# controllerHatMini.net
KiCad netlist of a schematic drawn in EAGLE
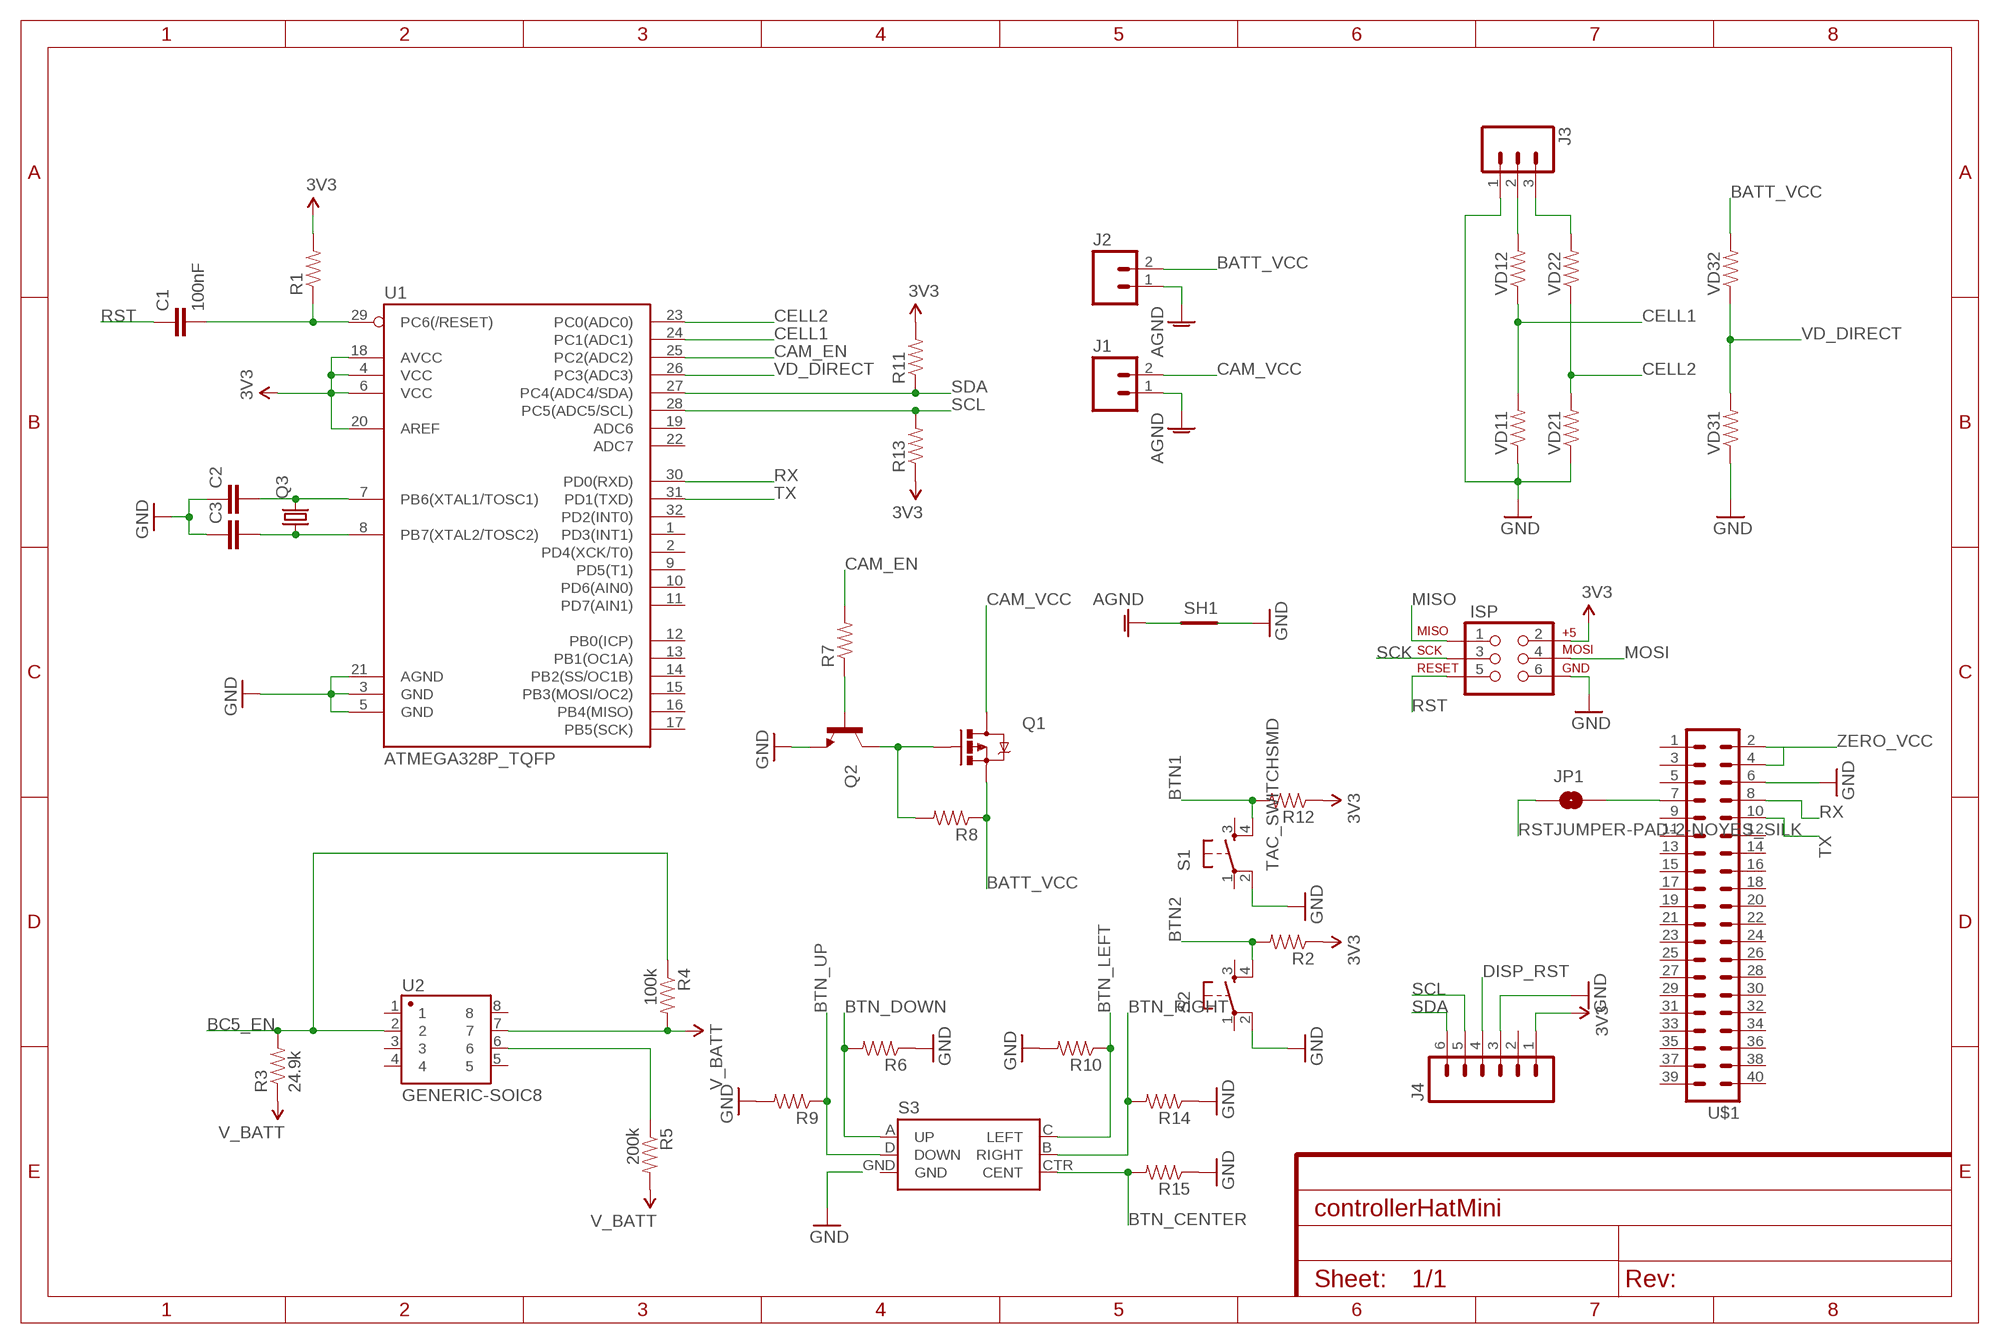
[diagram p0: schematic, sheet 1]

(export (version "E")
  (design (tool "Eeschema 10.0.6"))
  (components
    (comp (ref "C1")
      (value "100nF")
      (footprint "eagle-import:1206")
      (libsource (lib "eagle-import") (part "CAP1206"))
    )
    (comp (ref "C2")
      (value "CAP1206")
      (footprint "eagle-import:1206")
      (libsource (lib "eagle-import") (part "CAP1206"))
    )
    (comp (ref "C3")
      (value "CAP1206")
      (footprint "eagle-import:1206")
      (libsource (lib "eagle-import") (part "CAP1206"))
    )
    (comp (ref "ISP")
      (value "AVR_SPI_PRG_6PTH")
      (footprint "eagle-import:2X3")
      (libsource (lib "eagle-import") (part "AVR_SPI_PRG_6PTH"))
    )
    (comp (ref "J1")
      (value "M023.5MM_LOCK")
      (footprint "eagle-import:SCREWTERMINAL-3.5MM-2_LOCK")
      (libsource (lib "eagle-import") (part "M023.5MM_LOCK"))
    )
    (comp (ref "J2")
      (value "M023.5MM_LOCK")
      (footprint "eagle-import:SCREWTERMINAL-3.5MM-2_LOCK")
      (libsource (lib "eagle-import") (part "M023.5MM_LOCK"))
    )
    (comp (ref "J3")
      (value "M03LOCK")
      (footprint "eagle-import:1X03_LOCK")
      (libsource (lib "eagle-import") (part "M03LOCK"))
    )
    (comp (ref "J4")
      (value "M06LOCK")
      (footprint "eagle-import:1X06_LOCK")
      (libsource (lib "eagle-import") (part "M06LOCK"))
    )
    (comp (ref "JP1")
      (value "JUMPER-PAD-2-NOYES_SILK")
      (footprint "eagle-import:PAD-JUMPER-2-NO_YES_SILK")
      (libsource (lib "eagle-import") (part "JUMPER-PAD-2-NOYES_SILK"))
    )
    (comp (ref "Q1")
      (value "MOSFET-PCHANNELNDP6020P_20V_24A_LOW_VGS_TH")
      (footprint "eagle-import:TO220V")
      (libsource (lib "eagle-import") (part "MOSFET-PCHANNELNDP6020P_20V_24A_LOW_VGS_TH"))
    )
    (comp (ref "Q2")
      (value "TRANSISTOR_NPN2N3904")
      (footprint "eagle-import:TO-92")
      (libsource (lib "eagle-import") (part "TRANSISTOR_NPN2N3904"))
    )
    (comp (ref "Q3")
      (value "CRYSTALMM20SS")
      (footprint "eagle-import:MM20SS")
      (libsource (lib "eagle-import") (part "CRYSTALMM20SS"))
    )
    (comp (ref "R1")
      (value "RESISTOR1206")
      (footprint "eagle-import:1206")
      (libsource (lib "eagle-import") (part "RESISTOR1206"))
    )
    (comp (ref "R2")
      (value "RESISTOR1206")
      (footprint "eagle-import:1206")
      (libsource (lib "eagle-import") (part "RESISTOR1206"))
    )
    (comp (ref "R3")
      (value "24.9k")
      (footprint "eagle-import:1206")
      (libsource (lib "eagle-import") (part "RESISTOR1206"))
    )
    (comp (ref "R4")
      (value "100k")
      (footprint "eagle-import:1206")
      (libsource (lib "eagle-import") (part "RESISTOR1206"))
    )
    (comp (ref "R5")
      (value "200k")
      (footprint "eagle-import:1206")
      (libsource (lib "eagle-import") (part "RESISTOR1206"))
    )
    (comp (ref "R6")
      (value "RESISTOR1206")
      (footprint "eagle-import:1206")
      (libsource (lib "eagle-import") (part "RESISTOR1206"))
    )
    (comp (ref "R7")
      (value "RESISTOR1206")
      (footprint "eagle-import:1206")
      (libsource (lib "eagle-import") (part "RESISTOR1206"))
    )
    (comp (ref "R8")
      (value "RESISTOR1206")
      (footprint "eagle-import:1206")
      (libsource (lib "eagle-import") (part "RESISTOR1206"))
    )
    (comp (ref "R9")
      (value "RESISTOR1206")
      (footprint "eagle-import:1206")
      (libsource (lib "eagle-import") (part "RESISTOR1206"))
    )
    (comp (ref "R10")
      (value "RESISTOR1206")
      (footprint "eagle-import:1206")
      (libsource (lib "eagle-import") (part "RESISTOR1206"))
    )
    (comp (ref "R11")
      (value "RESISTOR1206")
      (footprint "eagle-import:1206")
      (libsource (lib "eagle-import") (part "RESISTOR1206"))
    )
    (comp (ref "R12")
      (value "RESISTOR1206")
      (footprint "eagle-import:1206")
      (libsource (lib "eagle-import") (part "RESISTOR1206"))
    )
    (comp (ref "R13")
      (value "RESISTOR1206")
      (footprint "eagle-import:1206")
      (libsource (lib "eagle-import") (part "RESISTOR1206"))
    )
    (comp (ref "R14")
      (value "RESISTOR1206")
      (footprint "eagle-import:1206")
      (libsource (lib "eagle-import") (part "RESISTOR1206"))
    )
    (comp (ref "R15")
      (value "RESISTOR1206")
      (footprint "eagle-import:1206")
      (libsource (lib "eagle-import") (part "RESISTOR1206"))
    )
    (comp (ref "S1")
      (value "TAC_SWITCHSMD")
      (footprint "eagle-import:TACTILE-PTH")
      (libsource (lib "eagle-import") (part "TAC_SWITCHPTH"))
    )
    (comp (ref "S2")
      (value "TAC_SWITCHPTH")
      (footprint "eagle-import:TACTILE-PTH")
      (libsource (lib "eagle-import") (part "TAC_SWITCHPTH"))
    )
    (comp (ref "S3")
      (value "JOYSTICK_MINI")
      (footprint "eagle-import:JOYSTICK_MINI")
      (libsource (lib "eagle-import") (part "JOYSTICK_MINI"))
    )
    (comp (ref "SH1")
      (value "SHORT-HT5")
      (footprint "eagle-import:SHORT_TOP-50")
      (libsource (lib "eagle-import") (part "SHORT-HT5"))
    )
    (comp (ref "U$1")
      (value "PIZERO_THROUGH_HOLE")
      (footprint "eagle-import:PIZERO_THOUGH_HOLE")
      (libsource (lib "eagle-import") (part "PIZERO_THROUGH_HOLE"))
    )
    (comp (ref "U1")
      (value "ATMEGA328P_TQFP")
      (footprint "eagle-import:TQFP32-08")
      (libsource (lib "eagle-import") (part "ATMEGA328P_TQFP"))
    )
    (comp (ref "U2")
      (value "GENERIC-SOIC8")
      (footprint "eagle-import:SO08-UNIVERSAL")
      (libsource (lib "eagle-import") (part "GENERIC-SOIC8"))
    )
    (comp (ref "VD11")
      (value "RESISTOR1206")
      (footprint "eagle-import:1206")
      (libsource (lib "eagle-import") (part "RESISTOR1206"))
    )
    (comp (ref "VD12")
      (value "RESISTOR1206")
      (footprint "eagle-import:1206")
      (libsource (lib "eagle-import") (part "RESISTOR1206"))
    )
    (comp (ref "VD21")
      (value "RESISTOR1206")
      (footprint "eagle-import:1206")
      (libsource (lib "eagle-import") (part "RESISTOR1206"))
    )
    (comp (ref "VD22")
      (value "RESISTOR1206")
      (footprint "eagle-import:1206")
      (libsource (lib "eagle-import") (part "RESISTOR1206"))
    )
    (comp (ref "VD31")
      (value "RESISTOR1206")
      (footprint "eagle-import:1206")
      (libsource (lib "eagle-import") (part "RESISTOR1206"))
    )
    (comp (ref "VD32")
      (value "RESISTOR1206")
      (footprint "eagle-import:1206")
      (libsource (lib "eagle-import") (part "RESISTOR1206"))
    )
  )
  (nets
    (net (code "1") (name "/BATT_VCC") (class "Default")
      (node (ref "J2") (pin "2") (pinfunction "2_2") (pintype "passive"))
      (node (ref "Q1") (pin "3") (pinfunction "S_3") (pintype "passive"))
      (node (ref "R8") (pin "1") (pinfunction "1_1") (pintype "passive"))
      (node (ref "VD32") (pin "2") (pinfunction "2_2") (pintype "passive"))
    )
    (net (code "2") (name "/BC5_EN") (class "Default")
      (node (ref "R3") (pin "2") (pinfunction "2_2") (pintype "passive"))
      (node (ref "R4") (pin "1") (pinfunction "1_1") (pintype "passive"))
      (node (ref "U2") (pin "2") (pinfunction "2_2") (pintype "bidirectional"))
    )
    (net (code "3") (name "/BTN1") (class "Default")
      (node (ref "R12") (pin "2") (pinfunction "2_2") (pintype "passive"))
      (node (ref "S1") (pin "4") (pinfunction "4_4") (pintype "passive"))
    )
    (net (code "4") (name "/BTN2") (class "Default")
      (node (ref "R2") (pin "2") (pinfunction "2_2") (pintype "passive"))
      (node (ref "S2") (pin "4") (pinfunction "4_4") (pintype "passive"))
    )
    (net (code "5") (name "/BTN_CENTER") (class "Default")
      (node (ref "R15") (pin "2") (pinfunction "2_2") (pintype "passive"))
      (node (ref "S3") (pin "CTR") (pinfunction "CENT_CTR") (pintype "bidirectional"))
    )
    (net (code "6") (name "/BTN_DOWN") (class "Default")
      (node (ref "R6") (pin "2") (pinfunction "2_2") (pintype "passive"))
      (node (ref "S3") (pin "A") (pinfunction "UP_A") (pintype "bidirectional"))
    )
    (net (code "7") (name "/BTN_LEFT") (class "Default")
      (node (ref "R10") (pin "1") (pinfunction "1_1") (pintype "passive"))
      (node (ref "S3") (pin "C") (pinfunction "LEFT_C") (pintype "bidirectional"))
    )
    (net (code "8") (name "/BTN_RIGHT") (class "Default")
      (node (ref "R14") (pin "2") (pinfunction "2_2") (pintype "passive"))
      (node (ref "S3") (pin "B") (pinfunction "RIGHT_B") (pintype "bidirectional"))
    )
    (net (code "9") (name "/BTN_UP") (class "Default")
      (node (ref "R9") (pin "1") (pinfunction "1_1") (pintype "passive"))
      (node (ref "S3") (pin "D") (pinfunction "DOWN_D") (pintype "bidirectional"))
    )
    (net (code "10") (name "/CAM_EN") (class "Default")
      (node (ref "R7") (pin "2") (pinfunction "2_2") (pintype "passive"))
      (node (ref "U1") (pin "25") (pinfunction "PC2(ADC2)_25") (pintype "bidirectional"))
    )
    (net (code "11") (name "/CAM_VCC") (class "Default")
      (node (ref "J1") (pin "2") (pinfunction "2_2") (pintype "passive"))
      (node (ref "Q1") (pin "2") (pinfunction "D_2") (pintype "passive"))
    )
    (net (code "12") (name "/CELL1") (class "Default")
      (node (ref "U1") (pin "24") (pinfunction "PC1(ADC1)_24") (pintype "bidirectional"))
      (node (ref "VD11") (pin "2") (pinfunction "2_2") (pintype "passive"))
      (node (ref "VD12") (pin "1") (pinfunction "1_1") (pintype "passive"))
    )
    (net (code "13") (name "/CELL2") (class "Default")
      (node (ref "U1") (pin "23") (pinfunction "PC0(ADC0)_23") (pintype "bidirectional"))
      (node (ref "VD21") (pin "2") (pinfunction "2_2") (pintype "passive"))
      (node (ref "VD22") (pin "1") (pinfunction "1_1") (pintype "passive"))
    )
    (net (code "14") (name "/DISP_RST") (class "Default")
      (node (ref "J4") (pin "4") (pinfunction "4_4") (pintype "passive"))
    )
    (net (code "15") (name "/MISO") (class "Default")
      (node (ref "ISP") (pin "1") (pinfunction "1_1") (pintype "passive"))
    )
    (net (code "16") (name "/MOSI") (class "Default")
      (node (ref "ISP") (pin "4") (pinfunction "4_4") (pintype "passive"))
    )
    (net (code "17") (name "/RST") (class "Default")
      (node (ref "C1") (pin "1") (pinfunction "1_1") (pintype "passive"))
      (node (ref "ISP") (pin "5") (pinfunction "5_5") (pintype "passive"))
      (node (ref "JP1") (pin "1") (pinfunction "1_1") (pintype "passive"))
    )
    (net (code "18") (name "/RX") (class "Default")
      (node (ref "U$1") (pin "8") (pinfunction "8_8") (pintype "passive"))
      (node (ref "U1") (pin "30") (pinfunction "PD0(RXD)_30") (pintype "bidirectional"))
    )
    (net (code "19") (name "/SCK") (class "Default")
      (node (ref "ISP") (pin "3") (pinfunction "3_3") (pintype "passive"))
    )
    (net (code "20") (name "/SCL") (class "Default")
      (node (ref "J4") (pin "5") (pinfunction "5_5") (pintype "passive"))
      (node (ref "R13") (pin "2") (pinfunction "2_2") (pintype "passive"))
      (node (ref "U1") (pin "28") (pinfunction "PC5(ADC5/SCL)_28") (pintype "bidirectional"))
    )
    (net (code "21") (name "/SDA") (class "Default")
      (node (ref "J4") (pin "6") (pinfunction "6_6") (pintype "passive"))
      (node (ref "R11") (pin "1") (pinfunction "1_1") (pintype "passive"))
      (node (ref "U1") (pin "27") (pinfunction "PC4(ADC4/SDA)_27") (pintype "bidirectional"))
    )
    (net (code "22") (name "/TX") (class "Default")
      (node (ref "U$1") (pin "10") (pinfunction "10_10") (pintype "passive"))
      (node (ref "U1") (pin "31") (pinfunction "PD1(TXD)_31") (pintype "bidirectional"))
    )
    (net (code "23") (name "/VD_DIRECT") (class "Default")
      (node (ref "U1") (pin "26") (pinfunction "PC3(ADC3)_26") (pintype "bidirectional"))
      (node (ref "VD31") (pin "2") (pinfunction "2_2") (pintype "passive"))
      (node (ref "VD32") (pin "1") (pinfunction "1_1") (pintype "passive"))
    )
    (net (code "24") (name "/ZERO_VCC") (class "Default")
      (node (ref "U$1") (pin "2") (pinfunction "2_2") (pintype "passive"))
    )
    (net (code "25") (name "3V3") (class "Default")
      (node (ref "ISP") (pin "2") (pinfunction "2_2") (pintype "passive"))
      (node (ref "J4") (pin "1") (pinfunction "1_1") (pintype "passive"))
      (node (ref "R1") (pin "2") (pinfunction "2_2") (pintype "passive"))
      (node (ref "R11") (pin "2") (pinfunction "2_2") (pintype "passive"))
      (node (ref "R12") (pin "1") (pinfunction "1_1") (pintype "passive"))
      (node (ref "R13") (pin "1") (pinfunction "1_1") (pintype "passive"))
      (node (ref "R2") (pin "1") (pinfunction "1_1") (pintype "passive"))
      (node (ref "U1") (pin "18") (pinfunction "AVCC_18") (pintype "bidirectional"))
      (node (ref "U1") (pin "20") (pinfunction "AREF_20") (pintype "bidirectional"))
      (node (ref "U1") (pin "4") (pinfunction "VCC_4") (pintype "bidirectional"))
      (node (ref "U1") (pin "6") (pinfunction "VCC_6") (pintype "bidirectional"))
    )
    (net (code "26") (name "AGND") (class "Default")
      (node (ref "J1") (pin "1") (pinfunction "1_1") (pintype "passive"))
      (node (ref "J2") (pin "1") (pinfunction "1_1") (pintype "passive"))
      (node (ref "SH1") (pin "1") (pinfunction "P$1_1") (pintype "bidirectional"))
    )
    (net (code "27") (name "GND") (class "Default")
      (node (ref "C2") (pin "1") (pinfunction "1_1") (pintype "passive"))
      (node (ref "C3") (pin "1") (pinfunction "1_1") (pintype "passive"))
      (node (ref "ISP") (pin "6") (pinfunction "6_6") (pintype "passive"))
      (node (ref "J3") (pin "1") (pinfunction "1_1") (pintype "passive"))
      (node (ref "J4") (pin "3") (pinfunction "3_3") (pintype "passive"))
      (node (ref "Q2") (pin "1") (pinfunction "E_1") (pintype "passive"))
      (node (ref "R10") (pin "2") (pinfunction "2_2") (pintype "passive"))
      (node (ref "R14") (pin "1") (pinfunction "1_1") (pintype "passive"))
      (node (ref "R15") (pin "1") (pinfunction "1_1") (pintype "passive"))
      (node (ref "R6") (pin "1") (pinfunction "1_1") (pintype "passive"))
      (node (ref "R9") (pin "2") (pinfunction "2_2") (pintype "passive"))
      (node (ref "S1") (pin "2") (pinfunction "2_2") (pintype "passive"))
      (node (ref "S2") (pin "2") (pinfunction "2_2") (pintype "passive"))
      (node (ref "SH1") (pin "2") (pinfunction "P$2_2") (pintype "bidirectional"))
      (node (ref "U$1") (pin "6") (pinfunction "6_6") (pintype "passive"))
      (node (ref "U1") (pin "21") (pinfunction "AGND_21") (pintype "bidirectional"))
      (node (ref "U1") (pin "3") (pinfunction "GND_3") (pintype "bidirectional"))
      (node (ref "U1") (pin "5") (pinfunction "GND_5") (pintype "bidirectional"))
      (node (ref "VD11") (pin "1") (pinfunction "1_1") (pintype "passive"))
      (node (ref "VD21") (pin "1") (pinfunction "1_1") (pintype "passive"))
      (node (ref "VD31") (pin "1") (pinfunction "1_1") (pintype "passive"))
    )
    (net (code "28") (name "Net-(J3-Pad2)") (class "Default")
      (node (ref "J3") (pin "2") (pinfunction "2_2") (pintype "passive"))
      (node (ref "VD12") (pin "2") (pinfunction "2_2") (pintype "passive"))
    )
    (net (code "29") (name "Net-(J3-Pad3)") (class "Default")
      (node (ref "J3") (pin "3") (pinfunction "3_3") (pintype "passive"))
      (node (ref "VD22") (pin "2") (pinfunction "2_2") (pintype "passive"))
    )
    (net (code "30") (name "Net-(JP1-Pad2)") (class "Default")
      (node (ref "JP1") (pin "2") (pinfunction "2_2") (pintype "passive"))
      (node (ref "U$1") (pin "7") (pinfunction "7_7") (pintype "passive"))
    )
    (net (code "31") (name "Net-(Q1-G)") (class "Default")
      (node (ref "Q1") (pin "1") (pinfunction "G_1") (pintype "passive"))
      (node (ref "Q2") (pin "3") (pinfunction "C_3") (pintype "passive"))
      (node (ref "R8") (pin "2") (pinfunction "2_2") (pintype "passive"))
    )
    (net (code "32") (name "Net-(Q2-B)") (class "Default")
      (node (ref "Q2") (pin "2") (pinfunction "B_2") (pintype "passive"))
      (node (ref "R7") (pin "1") (pinfunction "1_1") (pintype "passive"))
    )
    (net (code "33") (name "Net-(Q3-2)") (class "Default")
      (node (ref "C2") (pin "2") (pinfunction "2_2") (pintype "passive"))
      (node (ref "Q3") (pin "4") (pinfunction "2_4") (pintype "passive"))
      (node (ref "U1") (pin "7") (pinfunction "PB6(XTAL1/TOSC1)_7") (pintype "bidirectional"))
    )
    (net (code "34") (name "Net-(R5-Pad1)") (class "Default")
      (node (ref "R5") (pin "1") (pinfunction "1_1") (pintype "passive"))
      (node (ref "U2") (pin "6") (pinfunction "6_6") (pintype "bidirectional"))
    )
    (net (code "35") (name "Net-(U1-PB7(XTAL2{slash}TOSC2))") (class "Default")
      (node (ref "C3") (pin "2") (pinfunction "2_2") (pintype "passive"))
      (node (ref "Q3") (pin "1") (pinfunction "1_1") (pintype "passive"))
      (node (ref "U1") (pin "8") (pinfunction "PB7(XTAL2/TOSC2)_8") (pintype "bidirectional"))
    )
    (net (code "36") (name "Net-(U1-PC6({slash}RESET))") (class "Default")
      (node (ref "C1") (pin "2") (pinfunction "2_2") (pintype "passive"))
      (node (ref "R1") (pin "1") (pinfunction "1_1") (pintype "passive"))
      (node (ref "U1") (pin "29") (pinfunction "PC6(/RESET)_29") (pintype "bidirectional"))
    )
    (net (code "37") (name "V_BATT") (class "Default")
      (node (ref "R3") (pin "1") (pinfunction "1_1") (pintype "passive"))
      (node (ref "R4") (pin "2") (pinfunction "2_2") (pintype "passive"))
      (node (ref "R5") (pin "2") (pinfunction "2_2") (pintype "passive"))
      (node (ref "U2") (pin "7") (pinfunction "7_7") (pintype "bidirectional"))
    )
    (net (code "38") (name "unconnected-(J4-Pad2)") (class "Default")
      (node (ref "J4") (pin "2") (pinfunction "2_2") (pintype "passive"))
    )
    (net (code "39") (name "unconnected-(S1-Pad1)") (class "Default")
      (node (ref "S1") (pin "1") (pinfunction "1_1") (pintype "passive"))
    )
    (net (code "40") (name "unconnected-(S1-Pad3)") (class "Default")
      (node (ref "S1") (pin "3") (pinfunction "3_3") (pintype "passive"))
    )
    (net (code "41") (name "unconnected-(S2-Pad1)") (class "Default")
      (node (ref "S2") (pin "1") (pinfunction "1_1") (pintype "passive"))
    )
    (net (code "42") (name "unconnected-(S2-Pad3)") (class "Default")
      (node (ref "S2") (pin "3") (pinfunction "3_3") (pintype "passive"))
    )
    (net (code "43") (name "unconnected-(S3-PadGND)") (class "Default")
      (node (ref "S3") (pin "GND") (pinfunction "GND_GND") (pintype "bidirectional"))
    )
    (net (code "44") (name "unconnected-(U$1-Pad1)") (class "Default")
      (node (ref "U$1") (pin "1") (pinfunction "1_1") (pintype "passive"))
    )
    (net (code "45") (name "unconnected-(U$1-Pad3)") (class "Default")
      (node (ref "U$1") (pin "3") (pinfunction "3_3") (pintype "passive"))
    )
    (net (code "46") (name "unconnected-(U$1-Pad4)") (class "Default")
      (node (ref "U$1") (pin "4") (pinfunction "4_4") (pintype "passive"))
    )
    (net (code "47") (name "unconnected-(U$1-Pad5)") (class "Default")
      (node (ref "U$1") (pin "5") (pinfunction "5_5") (pintype "passive"))
    )
    (net (code "48") (name "unconnected-(U$1-Pad9)") (class "Default")
      (node (ref "U$1") (pin "9") (pinfunction "9_9") (pintype "passive"))
    )
    (net (code "49") (name "unconnected-(U$1-Pad11)") (class "Default")
      (node (ref "U$1") (pin "11") (pinfunction "11_11") (pintype "passive"))
    )
    (net (code "50") (name "unconnected-(U$1-Pad12)") (class "Default")
      (node (ref "U$1") (pin "12") (pinfunction "12_12") (pintype "passive"))
    )
    (net (code "51") (name "unconnected-(U$1-Pad13)") (class "Default")
      (node (ref "U$1") (pin "13") (pinfunction "13_13") (pintype "passive"))
    )
    (net (code "52") (name "unconnected-(U$1-Pad14)") (class "Default")
      (node (ref "U$1") (pin "14") (pinfunction "14_14") (pintype "passive"))
    )
    (net (code "53") (name "unconnected-(U$1-Pad15)") (class "Default")
      (node (ref "U$1") (pin "15") (pinfunction "15_15") (pintype "passive"))
    )
    (net (code "54") (name "unconnected-(U$1-Pad16)") (class "Default")
      (node (ref "U$1") (pin "16") (pinfunction "16_16") (pintype "passive"))
    )
    (net (code "55") (name "unconnected-(U$1-Pad17)") (class "Default")
      (node (ref "U$1") (pin "17") (pinfunction "17_17") (pintype "passive"))
    )
    (net (code "56") (name "unconnected-(U$1-Pad18)") (class "Default")
      (node (ref "U$1") (pin "18") (pinfunction "18_18") (pintype "passive"))
    )
    (net (code "57") (name "unconnected-(U$1-Pad19)") (class "Default")
      (node (ref "U$1") (pin "19") (pinfunction "19_19") (pintype "passive"))
    )
    (net (code "58") (name "unconnected-(U$1-Pad20)") (class "Default")
      (node (ref "U$1") (pin "20") (pinfunction "20_20") (pintype "passive"))
    )
    (net (code "59") (name "unconnected-(U$1-Pad21)") (class "Default")
      (node (ref "U$1") (pin "21") (pinfunction "21_21") (pintype "passive"))
    )
    (net (code "60") (name "unconnected-(U$1-Pad22)") (class "Default")
      (node (ref "U$1") (pin "22") (pinfunction "22_22") (pintype "passive"))
    )
    (net (code "61") (name "unconnected-(U$1-Pad23)") (class "Default")
      (node (ref "U$1") (pin "23") (pinfunction "23_23") (pintype "passive"))
    )
    (net (code "62") (name "unconnected-(U$1-Pad24)") (class "Default")
      (node (ref "U$1") (pin "24") (pinfunction "24_24") (pintype "passive"))
    )
    (net (code "63") (name "unconnected-(U$1-Pad25)") (class "Default")
      (node (ref "U$1") (pin "25") (pinfunction "25_25") (pintype "passive"))
    )
    (net (code "64") (name "unconnected-(U$1-Pad26)") (class "Default")
      (node (ref "U$1") (pin "26") (pinfunction "26_26") (pintype "passive"))
    )
    (net (code "65") (name "unconnected-(U$1-Pad27)") (class "Default")
      (node (ref "U$1") (pin "27") (pinfunction "27_27") (pintype "passive"))
    )
    (net (code "66") (name "unconnected-(U$1-Pad28)") (class "Default")
      (node (ref "U$1") (pin "28") (pinfunction "28_28") (pintype "passive"))
    )
    (net (code "67") (name "unconnected-(U$1-Pad29)") (class "Default")
      (node (ref "U$1") (pin "29") (pinfunction "29_29") (pintype "passive"))
    )
    (net (code "68") (name "unconnected-(U$1-Pad30)") (class "Default")
      (node (ref "U$1") (pin "30") (pinfunction "30_30") (pintype "passive"))
    )
    (net (code "69") (name "unconnected-(U$1-Pad31)") (class "Default")
      (node (ref "U$1") (pin "31") (pinfunction "31_31") (pintype "passive"))
    )
    (net (code "70") (name "unconnected-(U$1-Pad32)") (class "Default")
      (node (ref "U$1") (pin "32") (pinfunction "32_32") (pintype "passive"))
    )
    (net (code "71") (name "unconnected-(U$1-Pad33)") (class "Default")
      (node (ref "U$1") (pin "33") (pinfunction "33_33") (pintype "passive"))
    )
    (net (code "72") (name "unconnected-(U$1-Pad34)") (class "Default")
      (node (ref "U$1") (pin "34") (pinfunction "34_34") (pintype "passive"))
    )
    (net (code "73") (name "unconnected-(U$1-Pad35)") (class "Default")
      (node (ref "U$1") (pin "35") (pinfunction "35_35") (pintype "passive"))
    )
    (net (code "74") (name "unconnected-(U$1-Pad36)") (class "Default")
      (node (ref "U$1") (pin "36") (pinfunction "36_36") (pintype "passive"))
    )
    (net (code "75") (name "unconnected-(U$1-Pad37)") (class "Default")
      (node (ref "U$1") (pin "37") (pinfunction "37_37") (pintype "passive"))
    )
    (net (code "76") (name "unconnected-(U$1-Pad38)") (class "Default")
      (node (ref "U$1") (pin "38") (pinfunction "38_38") (pintype "passive"))
    )
    (net (code "77") (name "unconnected-(U$1-Pad39)") (class "Default")
      (node (ref "U$1") (pin "39") (pinfunction "39_39") (pintype "passive"))
    )
    (net (code "78") (name "unconnected-(U$1-Pad40)") (class "Default")
      (node (ref "U$1") (pin "40") (pinfunction "40_40") (pintype "passive"))
    )
    (net (code "79") (name "unconnected-(U1-ADC6-Pad19)") (class "Default")
      (node (ref "U1") (pin "19") (pinfunction "ADC6_19") (pintype "bidirectional"))
    )
    (net (code "80") (name "unconnected-(U1-ADC7-Pad22)") (class "Default")
      (node (ref "U1") (pin "22") (pinfunction "ADC7_22") (pintype "bidirectional"))
    )
    (net (code "81") (name "unconnected-(U1-PB0(ICP)-Pad12)") (class "Default")
      (node (ref "U1") (pin "12") (pinfunction "PB0(ICP)_12") (pintype "bidirectional"))
    )
    (net (code "82") (name "unconnected-(U1-PB1(OC1A)-Pad13)") (class "Default")
      (node (ref "U1") (pin "13") (pinfunction "PB1(OC1A)_13") (pintype "bidirectional"))
    )
    (net (code "83") (name "unconnected-(U1-PB2(SS{slash}OC1B)-Pad14)") (class "Default")
      (node (ref "U1") (pin "14") (pinfunction "PB2(SS/OC1B)_14") (pintype "bidirectional"))
    )
    (net (code "84") (name "unconnected-(U1-PB3(MOSI{slash}OC2)-Pad15)") (class "Default")
      (node (ref "U1") (pin "15") (pinfunction "PB3(MOSI/OC2)_15") (pintype "bidirectional"))
    )
    (net (code "85") (name "unconnected-(U1-PB4(MISO)-Pad16)") (class "Default")
      (node (ref "U1") (pin "16") (pinfunction "PB4(MISO)_16") (pintype "bidirectional"))
    )
    (net (code "86") (name "unconnected-(U1-PB5(SCK)-Pad17)") (class "Default")
      (node (ref "U1") (pin "17") (pinfunction "PB5(SCK)_17") (pintype "bidirectional"))
    )
    (net (code "87") (name "unconnected-(U1-PD2(INT0)-Pad32)") (class "Default")
      (node (ref "U1") (pin "32") (pinfunction "PD2(INT0)_32") (pintype "bidirectional"))
    )
    (net (code "88") (name "unconnected-(U1-PD3(INT1)-Pad1)") (class "Default")
      (node (ref "U1") (pin "1") (pinfunction "PD3(INT1)_1") (pintype "bidirectional"))
    )
    (net (code "89") (name "unconnected-(U1-PD4(XCK{slash}T0)-Pad2)") (class "Default")
      (node (ref "U1") (pin "2") (pinfunction "PD4(XCK/T0)_2") (pintype "bidirectional"))
    )
    (net (code "90") (name "unconnected-(U1-PD5(T1)-Pad9)") (class "Default")
      (node (ref "U1") (pin "9") (pinfunction "PD5(T1)_9") (pintype "bidirectional"))
    )
    (net (code "91") (name "unconnected-(U1-PD6(AIN0)-Pad10)") (class "Default")
      (node (ref "U1") (pin "10") (pinfunction "PD6(AIN0)_10") (pintype "bidirectional"))
    )
    (net (code "92") (name "unconnected-(U1-PD7(AIN1)-Pad11)") (class "Default")
      (node (ref "U1") (pin "11") (pinfunction "PD7(AIN1)_11") (pintype "bidirectional"))
    )
    (net (code "93") (name "unconnected-(U2-Pad1)") (class "Default")
      (node (ref "U2") (pin "1") (pinfunction "1_1") (pintype "bidirectional"))
    )
    (net (code "94") (name "unconnected-(U2-Pad3)") (class "Default")
      (node (ref "U2") (pin "3") (pinfunction "3_3") (pintype "bidirectional"))
    )
    (net (code "95") (name "unconnected-(U2-Pad4)") (class "Default")
      (node (ref "U2") (pin "4") (pinfunction "4_4") (pintype "bidirectional"))
    )
    (net (code "96") (name "unconnected-(U2-Pad5)") (class "Default")
      (node (ref "U2") (pin "5") (pinfunction "5_5") (pintype "bidirectional"))
    )
    (net (code "97") (name "unconnected-(U2-Pad8)") (class "Default")
      (node (ref "U2") (pin "8") (pinfunction "8_8") (pintype "bidirectional"))
    )
  )
)
